# Final_Bread_Proofing_Box_2020_05_07_A.net
KiCad netlist of a schematic drawn in EAGLE
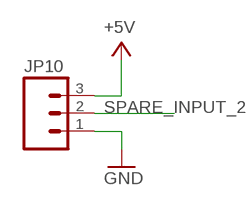
[diagram p0: schematic, sheet 1, part 1 of 2]
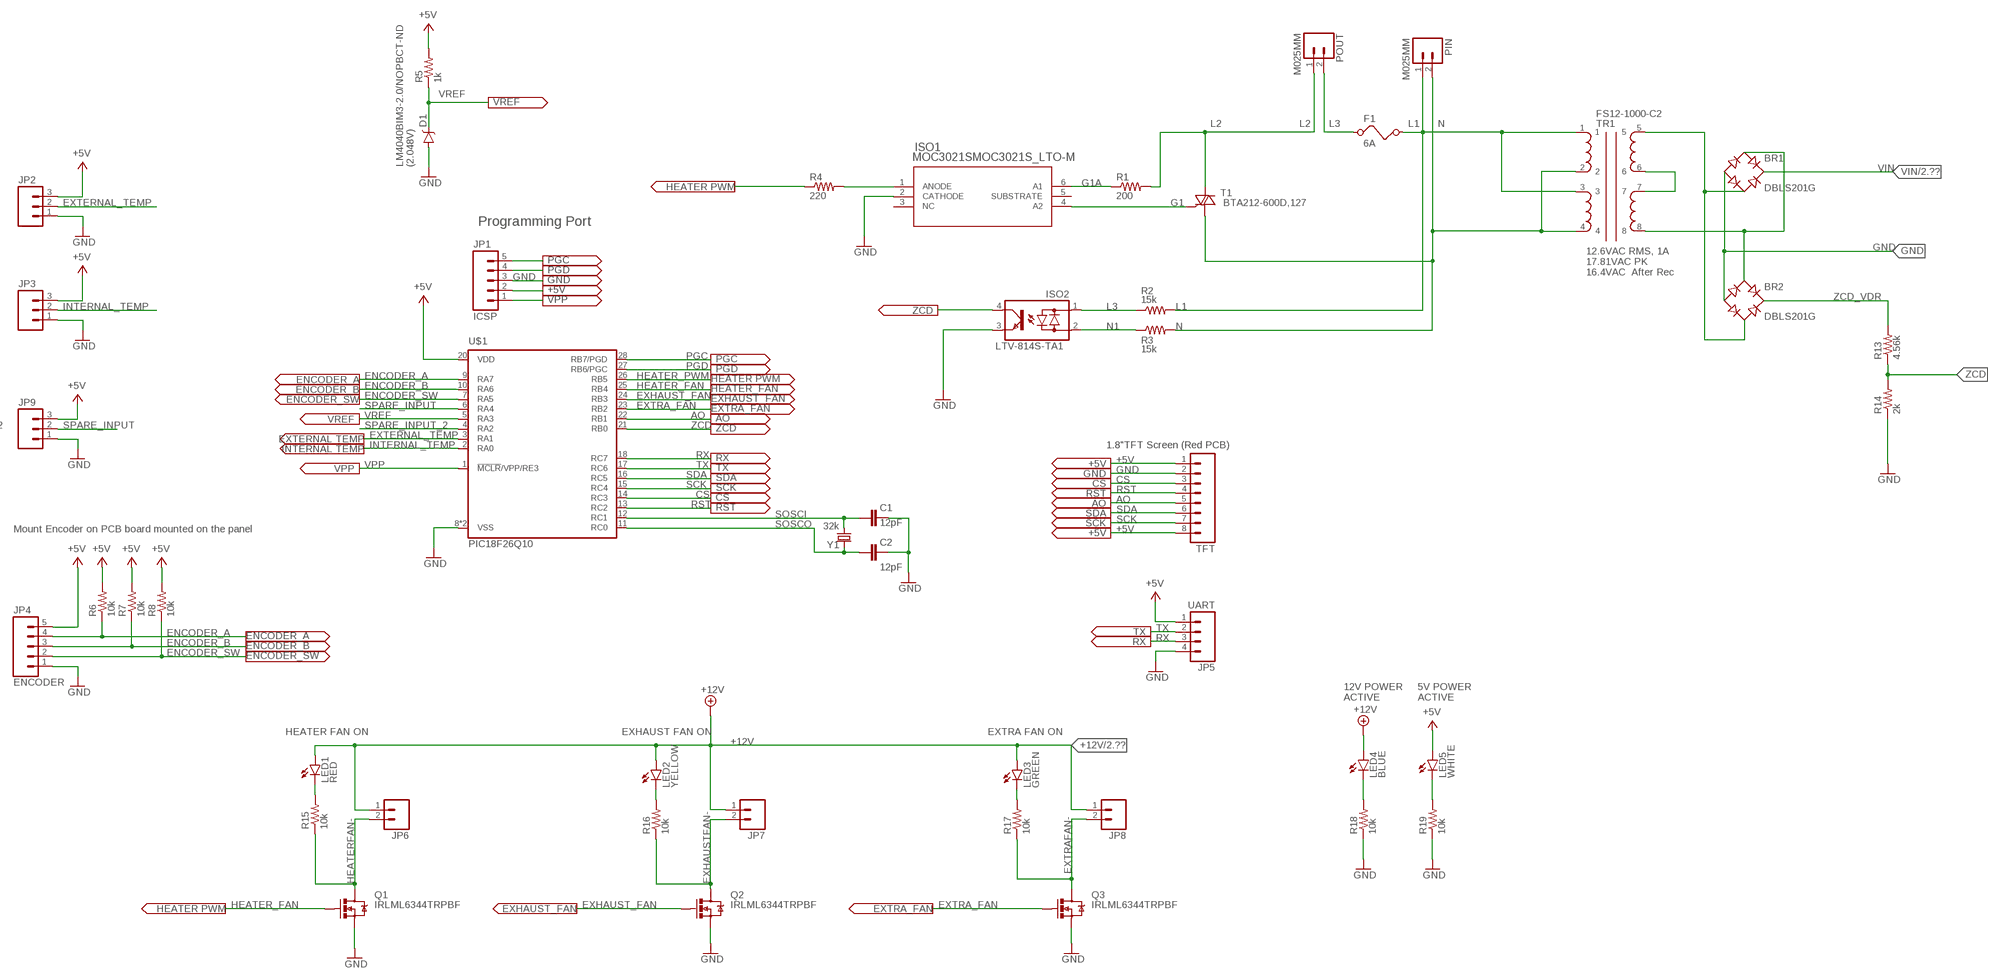
[diagram p1: schematic, sheet 1, part 2 of 2]
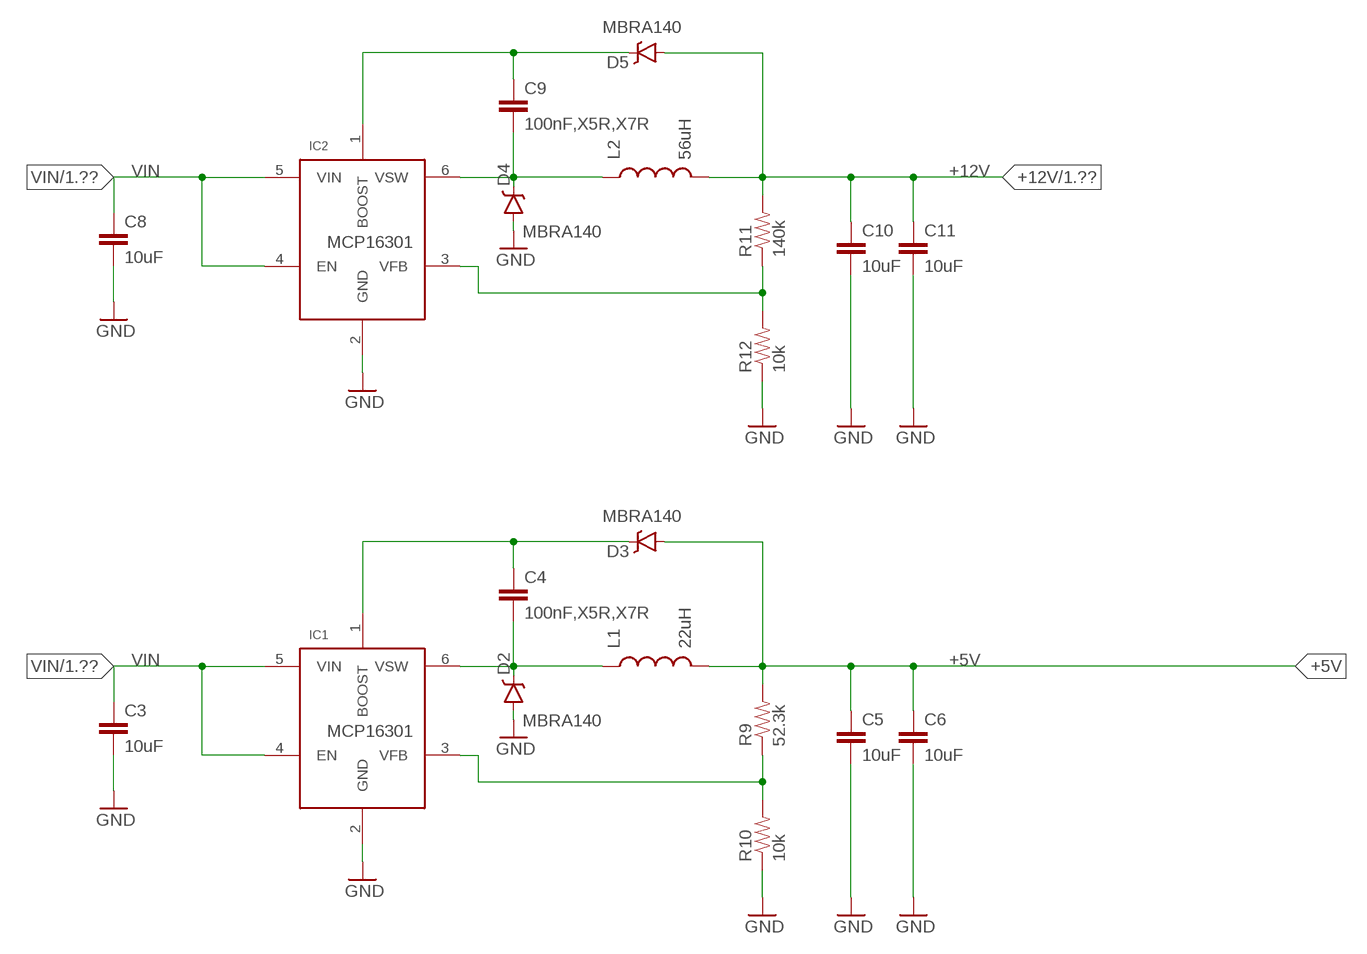
[diagram p2: schematic, sheet 2]

(export (version "E")
  (design (tool "Eeschema 10.0.6"))
  (components
    (comp (ref "BR1")
      (value "DBLS201G")
      (footprint "eagle-import:DBS")
      (libsource (lib "eagle-import") (part "DB?GLS201"))
    )
    (comp (ref "BR2")
      (value "DBLS201G")
      (footprint "eagle-import:DBS")
      (libsource (lib "eagle-import") (part "DB?GLS201"))
    )
    (comp (ref "C1")
      (value "12pF")
      (footprint "eagle-import:0805")
      (libsource (lib "eagle-import") (part "CAP0805"))
    )
    (comp (ref "C2")
      (value "12pF")
      (footprint "eagle-import:0805")
      (libsource (lib "eagle-import") (part "CAP0805"))
    )
    (comp (ref "D1")
      (value "V-REFERENCESMD")
      (footprint "eagle-import:SOT23-3")
      (libsource (lib "eagle-import") (part "V-REFERENCESMD"))
    )
    (comp (ref "F1")
      (value "6A")
      (footprint "eagle-import:FUSE")
      (libsource (lib "eagle-import") (part "FUSE"))
    )
    (comp (ref "ISO1")
      (value "MOC3021SMOC3021S_LTO-M")
      (footprint "eagle-import:MOC3021S_LTO-M")
      (fields
        (field (name "MANUFACTURER_PART_NUMBER") "MOC3021S")
        (field (name "COPYRIGHT") "Copyright (C) 2018 Accelerated Designs. All rights reserved")
      )
      (libsource (lib "eagle-import") (part "MOC3021SMOC3021S_LTO-M"))
    )
    (comp (ref "ISO2")
      (value "LTV-814S-TA1")
      (footprint "eagle-import:DIL4-SMD")
      (fields (field (name "MF") "VISHAY/TELEFUNKEN") (field (name "MPN") "SFH6206-3"))
      (libsource (lib "eagle-import") (part "SFH6206"))
    )
    (comp (ref "JP1")
      (value "ICSP")
      (footprint "eagle-import:1X05")
      (libsource (lib "eagle-import") (part "M05PTH"))
    )
    (comp (ref "JP2")
      (value "M03POLAR")
      (footprint "eagle-import:MOLEX-1X3")
      (libsource (lib "eagle-import") (part "M03POLAR"))
    )
    (comp (ref "JP3")
      (value "M03POLAR")
      (footprint "eagle-import:MOLEX-1X3")
      (libsource (lib "eagle-import") (part "M03POLAR"))
    )
    (comp (ref "JP4")
      (value "ENCODER")
      (footprint "eagle-import:1X05")
      (libsource (lib "eagle-import") (part "M05PTH"))
    )
    (comp (ref "JP5")
      (value "UART")
      (footprint "eagle-import:1X04_LOCK")
      (libsource (lib "eagle-import") (part "M04LOCK"))
    )
    (comp (ref "JP6")
      (value "M02POLAR_LOCK")
      (footprint "eagle-import:MOLEX-1X2_LOCK")
      (libsource (lib "eagle-import") (part "M02POLAR_LOCK"))
    )
    (comp (ref "JP7")
      (value "M02POLAR_LOCK")
      (footprint "eagle-import:MOLEX-1X2_LOCK")
      (libsource (lib "eagle-import") (part "M02POLAR_LOCK"))
    )
    (comp (ref "JP8")
      (value "M02POLAR_LOCK")
      (footprint "eagle-import:MOLEX-1X2_LOCK")
      (libsource (lib "eagle-import") (part "M02POLAR_LOCK"))
    )
    (comp (ref "JP9")
      (value "M03POLAR")
      (footprint "eagle-import:MOLEX-1X3")
      (libsource (lib "eagle-import") (part "M03POLAR"))
    )
    (comp (ref "JP10")
      (value "M03POLAR")
      (footprint "eagle-import:MOLEX-1X3")
      (libsource (lib "eagle-import") (part "M03POLAR"))
    )
    (comp (ref "LED1")
      (value "RED")
      (footprint "eagle-import:LED-1206")
      (libsource (lib "eagle-import") (part "LED1206"))
    )
    (comp (ref "LED2")
      (value "YELLOW")
      (footprint "eagle-import:LED-1206")
      (libsource (lib "eagle-import") (part "LED1206"))
    )
    (comp (ref "LED3")
      (value "GREEN")
      (footprint "eagle-import:LED-1206")
      (libsource (lib "eagle-import") (part "LED1206"))
    )
    (comp (ref "LED4")
      (value "BLUE")
      (footprint "eagle-import:LED-1206")
      (libsource (lib "eagle-import") (part "LED1206"))
    )
    (comp (ref "LED5")
      (value "WHITE")
      (footprint "eagle-import:LED-1206")
      (libsource (lib "eagle-import") (part "LED1206"))
    )
    (comp (ref "PIN")
      (value "M025MM")
      (footprint "eagle-import:SCREWTERMINAL-5MM-2")
      (libsource (lib "eagle-import") (part "M025MM"))
    )
    (comp (ref "POUT")
      (value "M025MM")
      (footprint "eagle-import:SCREWTERMINAL-5MM-2")
      (libsource (lib "eagle-import") (part "M025MM"))
    )
    (comp (ref "Q1")
      (value "IRLML6344TRPBF")
      (footprint "eagle-import:SOT323")
      (libsource (lib "eagle-import") (part "MOSFET-NCHANNEL2N7002PW"))
    )
    (comp (ref "Q2")
      (value "IRLML6344TRPBF")
      (footprint "eagle-import:SOT323")
      (libsource (lib "eagle-import") (part "MOSFET-NCHANNEL2N7002PW"))
    )
    (comp (ref "Q3")
      (value "IRLML6344TRPBF")
      (footprint "eagle-import:SOT323")
      (libsource (lib "eagle-import") (part "MOSFET-NCHANNEL2N7002PW"))
    )
    (comp (ref "R1")
      (value "200")
      (footprint "eagle-import:R2512")
      (libsource (lib "eagle-import") (part "R-US_R2512"))
    )
    (comp (ref "R2")
      (value "15k")
      (footprint "eagle-import:R2512")
      (libsource (lib "eagle-import") (part "R-US_R2512"))
    )
    (comp (ref "R3")
      (value "15k")
      (footprint "eagle-import:R2512")
      (libsource (lib "eagle-import") (part "R-US_R2512"))
    )
    (comp (ref "R4")
      (value "220")
      (footprint "eagle-import:1206")
      (libsource (lib "eagle-import") (part "RESISTOR1206"))
    )
    (comp (ref "R5")
      (value "1k")
      (footprint "eagle-import:1206")
      (libsource (lib "eagle-import") (part "RESISTOR1206"))
    )
    (comp (ref "R6")
      (value "10k")
      (footprint "eagle-import:1206")
      (libsource (lib "eagle-import") (part "RESISTOR1206"))
    )
    (comp (ref "R7")
      (value "10k")
      (footprint "eagle-import:1206")
      (libsource (lib "eagle-import") (part "RESISTOR1206"))
    )
    (comp (ref "R8")
      (value "10k")
      (footprint "eagle-import:1206")
      (libsource (lib "eagle-import") (part "RESISTOR1206"))
    )
    (comp (ref "R13")
      (value "4.56k")
      (footprint "eagle-import:1206")
      (libsource (lib "eagle-import") (part "RESISTOR1206"))
    )
    (comp (ref "R14")
      (value "2k")
      (footprint "eagle-import:1206")
      (libsource (lib "eagle-import") (part "RESISTOR1206"))
    )
    (comp (ref "R15")
      (value "10k")
      (footprint "eagle-import:1206")
      (libsource (lib "eagle-import") (part "RESISTOR1206"))
    )
    (comp (ref "R16")
      (value "10k")
      (footprint "eagle-import:1206")
      (libsource (lib "eagle-import") (part "RESISTOR1206"))
    )
    (comp (ref "R17")
      (value "10k")
      (footprint "eagle-import:1206")
      (libsource (lib "eagle-import") (part "RESISTOR1206"))
    )
    (comp (ref "R18")
      (value "10k")
      (footprint "eagle-import:1206")
      (libsource (lib "eagle-import") (part "RESISTOR1206"))
    )
    (comp (ref "R19")
      (value "10k")
      (footprint "eagle-import:1206")
      (libsource (lib "eagle-import") (part "RESISTOR1206"))
    )
    (comp (ref "T1")
      (value "BTA212-600D,127")
      (footprint "eagle-import:TO220BV")
      (libsource (lib "eagle-import") (part "BT138-V"))
    )
    (comp (ref "TFT")
      (value "M08LOCK")
      (footprint "eagle-import:1X08_LOCK")
      (libsource (lib "eagle-import") (part "M08LOCK"))
    )
    (comp (ref "TR1")
      (value "FS12-1000-C2")
      (footprint "eagle-import:FS12-1000-C2")
      (libsource (lib "eagle-import") (part "FS12-1000-C2"))
    )
    (comp (ref "U$1")
      (value "PIC18F26Q10")
      (footprint "eagle-import:SO28W")
      (libsource (lib "eagle-import") (part "PIC18F25K22SOIC"))
    )
    (comp (ref "Y1")
      (value "32k")
      (footprint "eagle-import:TC26V")
      (libsource (lib "eagle-import") (part "CRYSTALTC26V"))
    )
    (comp (ref "C3")
      (value "10uF")
      (footprint "eagle-import:1206")
      (libsource (lib "eagle-import") (part "CAP1206"))
    )
    (comp (ref "C4")
      (value "100nF,X5R,X7R")
      (footprint "eagle-import:1206")
      (libsource (lib "eagle-import") (part "CAP1206"))
    )
    (comp (ref "C5")
      (value "10uF")
      (footprint "eagle-import:1206")
      (libsource (lib "eagle-import") (part "CAP1206"))
    )
    (comp (ref "C6")
      (value "10uF")
      (footprint "eagle-import:1206")
      (libsource (lib "eagle-import") (part "CAP1206"))
    )
    (comp (ref "C8")
      (value "10uF")
      (footprint "eagle-import:1206")
      (libsource (lib "eagle-import") (part "CAP1206"))
    )
    (comp (ref "C9")
      (value "100nF,X5R,X7R")
      (footprint "eagle-import:1206")
      (libsource (lib "eagle-import") (part "CAP1206"))
    )
    (comp (ref "C10")
      (value "10uF")
      (footprint "eagle-import:1206")
      (libsource (lib "eagle-import") (part "CAP1206"))
    )
    (comp (ref "C11")
      (value "10uF")
      (footprint "eagle-import:1206")
      (libsource (lib "eagle-import") (part "CAP1206"))
    )
    (comp (ref "D2")
      (value "MBRA140")
      (footprint "eagle-import:SMA-DIODE")
      (libsource (lib "eagle-import") (part "DIODE-SCHOTTKY-MBRA140"))
    )
    (comp (ref "D3")
      (value "MBRA140")
      (footprint "eagle-import:SMA-DIODE")
      (libsource (lib "eagle-import") (part "DIODE-SCHOTTKY-MBRA140"))
    )
    (comp (ref "D4")
      (value "MBRA140")
      (footprint "eagle-import:SMA-DIODE")
      (libsource (lib "eagle-import") (part "DIODE-SCHOTTKY-MBRA140"))
    )
    (comp (ref "D5")
      (value "MBRA140")
      (footprint "eagle-import:SMA-DIODE")
      (libsource (lib "eagle-import") (part "DIODE-SCHOTTKY-MBRA140"))
    )
    (comp (ref "IC1")
      (value "MCP16301")
      (footprint "eagle-import:SOT23-6")
      (libsource (lib "eagle-import") (part "MCP16301"))
    )
    (comp (ref "IC2")
      (value "MCP16301")
      (footprint "eagle-import:SOT23-6")
      (libsource (lib "eagle-import") (part "MCP16301"))
    )
    (comp (ref "L1")
      (value "22uH")
      (footprint "eagle-import:1210")
      (libsource (lib "eagle-import") (part "INDUCTOR1210"))
    )
    (comp (ref "L2")
      (value "56uH")
      (footprint "eagle-import:1210")
      (libsource (lib "eagle-import") (part "INDUCTOR1210"))
    )
    (comp (ref "R9")
      (value "52.3k")
      (footprint "eagle-import:1206")
      (libsource (lib "eagle-import") (part "RESISTOR1206"))
    )
    (comp (ref "R10")
      (value "10k")
      (footprint "eagle-import:1206")
      (libsource (lib "eagle-import") (part "RESISTOR1206"))
    )
    (comp (ref "R11")
      (value "140k")
      (footprint "eagle-import:1206")
      (libsource (lib "eagle-import") (part "RESISTOR1206"))
    )
    (comp (ref "R12")
      (value "10k")
      (footprint "eagle-import:1206")
      (libsource (lib "eagle-import") (part "RESISTOR1206"))
    )
  )
  (nets
    (net (code "1") (name "+5V") (class "Default")
      (node (ref "C5") (pin "1") (pinfunction "1_1") (pintype "passive"))
      (node (ref "C6") (pin "1") (pinfunction "1_1") (pintype "passive"))
      (node (ref "D3") (pin "A") (pinfunction "A_A") (pintype "passive"))
      (node (ref "JP1") (pin "2") (pinfunction "2_2") (pintype "passive"))
      (node (ref "JP10") (pin "3") (pinfunction "3_3") (pintype "passive"))
      (node (ref "JP2") (pin "3") (pinfunction "3_3") (pintype "passive"))
      (node (ref "JP3") (pin "3") (pinfunction "3_3") (pintype "passive"))
      (node (ref "JP4") (pin "5") (pinfunction "5_5") (pintype "passive"))
      (node (ref "JP5") (pin "1") (pinfunction "1_1") (pintype "passive"))
      (node (ref "JP9") (pin "3") (pinfunction "3_3") (pintype "passive"))
      (node (ref "L1") (pin "2") (pinfunction "2_2") (pintype "passive"))
      (node (ref "LED5") (pin "A") (pinfunction "A_A") (pintype "passive"))
      (node (ref "R5") (pin "2") (pinfunction "2_2") (pintype "passive"))
      (node (ref "R6") (pin "2") (pinfunction "2_2") (pintype "passive"))
      (node (ref "R7") (pin "2") (pinfunction "2_2") (pintype "passive"))
      (node (ref "R8") (pin "2") (pinfunction "2_2") (pintype "passive"))
      (node (ref "R9") (pin "2") (pinfunction "2_2") (pintype "passive"))
      (node (ref "TFT") (pin "1") (pinfunction "1_1") (pintype "passive"))
      (node (ref "TFT") (pin "8") (pinfunction "8_8") (pintype "passive"))
      (node (ref "U$1") (pin "20") (pinfunction "VDD_20") (pintype "power_in"))
    )
    (net (code "2") (name "+12V") (class "Default")
      (node (ref "C10") (pin "1") (pinfunction "1_1") (pintype "passive"))
      (node (ref "C11") (pin "1") (pinfunction "1_1") (pintype "passive"))
      (node (ref "D5") (pin "A") (pinfunction "A_A") (pintype "passive"))
      (node (ref "JP6") (pin "1") (pinfunction "1_1") (pintype "passive"))
      (node (ref "JP7") (pin "1") (pinfunction "1_1") (pintype "passive"))
      (node (ref "JP8") (pin "1") (pinfunction "1_1") (pintype "passive"))
      (node (ref "L2") (pin "2") (pinfunction "2_2") (pintype "passive"))
      (node (ref "LED1") (pin "A") (pinfunction "A_A") (pintype "passive"))
      (node (ref "LED2") (pin "A") (pinfunction "A_A") (pintype "passive"))
      (node (ref "LED3") (pin "A") (pinfunction "A_A") (pintype "passive"))
      (node (ref "LED4") (pin "A") (pinfunction "A_A") (pintype "passive"))
      (node (ref "R11") (pin "2") (pinfunction "2_2") (pintype "passive"))
    )
    (net (code "3") (name "AO") (class "Default")
      (node (ref "TFT") (pin "5") (pinfunction "5_5") (pintype "passive"))
      (node (ref "U$1") (pin "22") (pinfunction "RB1_22") (pintype "bidirectional"))
    )
    (net (code "4") (name "CS") (class "Default")
      (node (ref "TFT") (pin "3") (pinfunction "3_3") (pintype "passive"))
      (node (ref "U$1") (pin "14") (pinfunction "RC3_14") (pintype "bidirectional"))
    )
    (net (code "5") (name "ENCODER_A") (class "Default")
      (node (ref "JP4") (pin "4") (pinfunction "4_4") (pintype "passive"))
      (node (ref "R6") (pin "1") (pinfunction "1_1") (pintype "passive"))
      (node (ref "U$1") (pin "9") (pinfunction "RA7_9") (pintype "bidirectional"))
    )
    (net (code "6") (name "ENCODER_B") (class "Default")
      (node (ref "JP4") (pin "3") (pinfunction "3_3") (pintype "passive"))
      (node (ref "R7") (pin "1") (pinfunction "1_1") (pintype "passive"))
      (node (ref "U$1") (pin "10") (pinfunction "RA6_10") (pintype "bidirectional"))
    )
    (net (code "7") (name "ENCODER_SW") (class "Default")
      (node (ref "JP4") (pin "2") (pinfunction "2_2") (pintype "passive"))
      (node (ref "R8") (pin "1") (pinfunction "1_1") (pintype "passive"))
      (node (ref "U$1") (pin "7") (pinfunction "RA5_7") (pintype "bidirectional"))
    )
    (net (code "8") (name "EXHAUSTFAN-") (class "Default")
      (node (ref "JP7") (pin "2") (pinfunction "2_2") (pintype "passive"))
      (node (ref "Q2") (pin "3") (pinfunction "D_3") (pintype "passive"))
      (node (ref "R16") (pin "1") (pinfunction "1_1") (pintype "passive"))
    )
    (net (code "9") (name "EXHAUST_FAN") (class "Default")
      (node (ref "Q2") (pin "1") (pinfunction "G_1") (pintype "passive"))
      (node (ref "U$1") (pin "24") (pinfunction "RB3_24") (pintype "bidirectional"))
    )
    (net (code "10") (name "EXTERNAL_TEMP") (class "Default")
      (node (ref "JP2") (pin "2") (pinfunction "2_2") (pintype "passive"))
      (node (ref "U$1") (pin "3") (pinfunction "RA1_3") (pintype "bidirectional"))
    )
    (net (code "11") (name "EXTRAFAN-") (class "Default")
      (node (ref "JP8") (pin "2") (pinfunction "2_2") (pintype "passive"))
      (node (ref "Q3") (pin "3") (pinfunction "D_3") (pintype "passive"))
      (node (ref "R17") (pin "1") (pinfunction "1_1") (pintype "passive"))
    )
    (net (code "12") (name "EXTRA_FAN") (class "Default")
      (node (ref "Q3") (pin "1") (pinfunction "G_1") (pintype "passive"))
      (node (ref "U$1") (pin "23") (pinfunction "RB2_23") (pintype "bidirectional"))
    )
    (net (code "13") (name "G1") (class "Default")
      (node (ref "ISO1") (pin "4") (pinfunction "A2_4") (pintype "passive"))
      (node (ref "T1") (pin "G") (pinfunction "G_G") (pintype "passive"))
    )
    (net (code "14") (name "G1A") (class "Default")
      (node (ref "ISO1") (pin "6") (pinfunction "A1_6") (pintype "passive"))
      (node (ref "R1") (pin "1") (pinfunction "1_1") (pintype "passive"))
    )
    (net (code "15") (name "GND") (class "Default")
      (node (ref "BR1") (pin "-") (pinfunction "-_-") (pintype "passive"))
      (node (ref "BR2") (pin "-") (pinfunction "-_-") (pintype "passive"))
      (node (ref "C1") (pin "2") (pinfunction "2_2") (pintype "passive"))
      (node (ref "C10") (pin "2") (pinfunction "2_2") (pintype "passive"))
      (node (ref "C11") (pin "2") (pinfunction "2_2") (pintype "passive"))
      (node (ref "C2") (pin "2") (pinfunction "2_2") (pintype "passive"))
      (node (ref "C3") (pin "2") (pinfunction "2_2") (pintype "passive"))
      (node (ref "C5") (pin "2") (pinfunction "2_2") (pintype "passive"))
      (node (ref "C6") (pin "2") (pinfunction "2_2") (pintype "passive"))
      (node (ref "C8") (pin "2") (pinfunction "2_2") (pintype "passive"))
      (node (ref "D1") (pin "2") (pinfunction "A_2") (pintype "passive"))
      (node (ref "D2") (pin "A") (pinfunction "A_A") (pintype "passive"))
      (node (ref "D4") (pin "A") (pinfunction "A_A") (pintype "passive"))
      (node (ref "IC1") (pin "2") (pinfunction "GND_2") (pintype "bidirectional"))
      (node (ref "IC2") (pin "2") (pinfunction "GND_2") (pintype "bidirectional"))
      (node (ref "ISO1") (pin "2") (pinfunction "CATHODE_2") (pintype "passive"))
      (node (ref "ISO2") (pin "3") (pinfunction "E_3") (pintype "passive"))
      (node (ref "JP1") (pin "3") (pinfunction "3_3") (pintype "passive"))
      (node (ref "JP10") (pin "1") (pinfunction "1_1") (pintype "passive"))
      (node (ref "JP2") (pin "1") (pinfunction "1_1") (pintype "passive"))
      (node (ref "JP3") (pin "1") (pinfunction "1_1") (pintype "passive"))
      (node (ref "JP4") (pin "1") (pinfunction "1_1") (pintype "passive"))
      (node (ref "JP5") (pin "4") (pinfunction "4_4") (pintype "passive"))
      (node (ref "JP9") (pin "1") (pinfunction "1_1") (pintype "passive"))
      (node (ref "Q1") (pin "2") (pinfunction "S_2") (pintype "passive"))
      (node (ref "Q2") (pin "2") (pinfunction "S_2") (pintype "passive"))
      (node (ref "Q3") (pin "2") (pinfunction "S_2") (pintype "passive"))
      (node (ref "R10") (pin "1") (pinfunction "1_1") (pintype "passive"))
      (node (ref "R12") (pin "1") (pinfunction "1_1") (pintype "passive"))
      (node (ref "R14") (pin "1") (pinfunction "1_1") (pintype "passive"))
      (node (ref "R18") (pin "1") (pinfunction "1_1") (pintype "passive"))
      (node (ref "R19") (pin "1") (pinfunction "1_1") (pintype "passive"))
      (node (ref "TFT") (pin "2") (pinfunction "2_2") (pintype "passive"))
      (node (ref "U$1") (pin "19") (pinfunction "VSS_19") (pintype "power_in"))
      (node (ref "U$1") (pin "8") (pinfunction "VSS_8") (pintype "power_in"))
    )
    (net (code "16") (name "HEATERFAN-") (class "Default")
      (node (ref "JP6") (pin "2") (pinfunction "2_2") (pintype "passive"))
      (node (ref "Q1") (pin "3") (pinfunction "D_3") (pintype "passive"))
      (node (ref "R15") (pin "1") (pinfunction "1_1") (pintype "passive"))
    )
    (net (code "17") (name "HEATER_FAN") (class "Default")
      (node (ref "Q1") (pin "1") (pinfunction "G_1") (pintype "passive"))
      (node (ref "U$1") (pin "25") (pinfunction "RB4_25") (pintype "bidirectional"))
    )
    (net (code "18") (name "HEATER_PWM") (class "Default")
      (node (ref "R4") (pin "1") (pinfunction "1_1") (pintype "passive"))
      (node (ref "U$1") (pin "26") (pinfunction "RB5_26") (pintype "bidirectional"))
    )
    (net (code "19") (name "INTERNAL_TEMP") (class "Default")
      (node (ref "JP3") (pin "2") (pinfunction "2_2") (pintype "passive"))
      (node (ref "U$1") (pin "2") (pinfunction "RA0_2") (pintype "bidirectional"))
    )
    (net (code "20") (name "L1") (class "Default")
      (node (ref "F1") (pin "2") (pinfunction "2_2") (pintype "passive"))
      (node (ref "PIN") (pin "1") (pinfunction "1_1") (pintype "passive"))
      (node (ref "R2") (pin "2") (pinfunction "2_2") (pintype "passive"))
      (node (ref "TR1") (pin "1") (pinfunction "1_1") (pintype "passive"))
      (node (ref "TR1") (pin "3") (pinfunction "3_3") (pintype "passive"))
    )
    (net (code "21") (name "L2") (class "Default")
      (node (ref "POUT") (pin "1") (pinfunction "1_1") (pintype "passive"))
      (node (ref "R1") (pin "2") (pinfunction "2_2") (pintype "passive"))
      (node (ref "T1") (pin "T2") (pinfunction "A2_T2") (pintype "passive"))
    )
    (net (code "22") (name "L3") (class "Default")
      (node (ref "F1") (pin "1") (pinfunction "1_1") (pintype "passive"))
      (node (ref "ISO2") (pin "1") (pinfunction "AC1_1") (pintype "passive"))
      (node (ref "POUT") (pin "2") (pinfunction "2_2") (pintype "passive"))
      (node (ref "R2") (pin "1") (pinfunction "1_1") (pintype "passive"))
    )
    (net (code "23") (name "N") (class "Default")
      (node (ref "PIN") (pin "2") (pinfunction "2_2") (pintype "passive"))
      (node (ref "R3") (pin "2") (pinfunction "2_2") (pintype "passive"))
      (node (ref "T1") (pin "T1") (pinfunction "A1_T1") (pintype "passive"))
      (node (ref "TR1") (pin "2") (pinfunction "2_2") (pintype "passive"))
      (node (ref "TR1") (pin "4") (pinfunction "4_4") (pintype "passive"))
    )
    (net (code "24") (name "N1") (class "Default")
      (node (ref "ISO2") (pin "2") (pinfunction "AC2_2") (pintype "passive"))
      (node (ref "R3") (pin "1") (pinfunction "1_1") (pintype "passive"))
    )
    (net (code "25") (name "Net-(BR1-PadAC1)") (class "Default")
      (node (ref "BR1") (pin "AC1") (pinfunction "AC1_AC1") (pintype "passive"))
      (node (ref "BR2") (pin "AC1") (pinfunction "AC1_AC1") (pintype "passive"))
      (node (ref "TR1") (pin "8") (pinfunction "8_8") (pintype "bidirectional"))
    )
    (net (code "26") (name "Net-(BR1-PadAC2)") (class "Default")
      (node (ref "BR1") (pin "AC2") (pinfunction "AC2_AC2") (pintype "passive"))
      (node (ref "BR2") (pin "AC2") (pinfunction "AC2_AC2") (pintype "passive"))
      (node (ref "TR1") (pin "5") (pinfunction "5_5") (pintype "bidirectional"))
    )
    (net (code "27") (name "Net-(IC1-BOOST)") (class "Default")
      (node (ref "C4") (pin "1") (pinfunction "1_1") (pintype "passive"))
      (node (ref "D3") (pin "C") (pinfunction "C_C") (pintype "passive"))
      (node (ref "IC1") (pin "1") (pinfunction "BOOST_1") (pintype "bidirectional"))
    )
    (net (code "28") (name "Net-(IC1-VFB)") (class "Default")
      (node (ref "IC1") (pin "3") (pinfunction "VFB_3") (pintype "bidirectional"))
      (node (ref "R10") (pin "2") (pinfunction "2_2") (pintype "passive"))
      (node (ref "R9") (pin "1") (pinfunction "1_1") (pintype "passive"))
    )
    (net (code "29") (name "Net-(IC1-VSW)") (class "Default")
      (node (ref "C4") (pin "2") (pinfunction "2_2") (pintype "passive"))
      (node (ref "D2") (pin "C") (pinfunction "C_C") (pintype "passive"))
      (node (ref "IC1") (pin "6") (pinfunction "VSW_6") (pintype "bidirectional"))
      (node (ref "L1") (pin "1") (pinfunction "1_1") (pintype "passive"))
    )
    (net (code "30") (name "Net-(IC2-BOOST)") (class "Default")
      (node (ref "C9") (pin "1") (pinfunction "1_1") (pintype "passive"))
      (node (ref "D5") (pin "C") (pinfunction "C_C") (pintype "passive"))
      (node (ref "IC2") (pin "1") (pinfunction "BOOST_1") (pintype "bidirectional"))
    )
    (net (code "31") (name "Net-(IC2-VFB)") (class "Default")
      (node (ref "IC2") (pin "3") (pinfunction "VFB_3") (pintype "bidirectional"))
      (node (ref "R11") (pin "1") (pinfunction "1_1") (pintype "passive"))
      (node (ref "R12") (pin "2") (pinfunction "2_2") (pintype "passive"))
    )
    (net (code "32") (name "Net-(IC2-VSW)") (class "Default")
      (node (ref "C9") (pin "2") (pinfunction "2_2") (pintype "passive"))
      (node (ref "D4") (pin "C") (pinfunction "C_C") (pintype "passive"))
      (node (ref "IC2") (pin "6") (pinfunction "VSW_6") (pintype "bidirectional"))
      (node (ref "L2") (pin "1") (pinfunction "1_1") (pintype "passive"))
    )
    (net (code "33") (name "Net-(ISO1-ANODE)") (class "Default")
      (node (ref "ISO1") (pin "1") (pinfunction "ANODE_1") (pintype "passive"))
      (node (ref "R4") (pin "2") (pinfunction "2_2") (pintype "passive"))
    )
    (net (code "34") (name "Net-(LED1-PadC)") (class "Default")
      (node (ref "LED1") (pin "C") (pinfunction "C_C") (pintype "passive"))
      (node (ref "R15") (pin "2") (pinfunction "2_2") (pintype "passive"))
    )
    (net (code "35") (name "Net-(LED2-PadC)") (class "Default")
      (node (ref "LED2") (pin "C") (pinfunction "C_C") (pintype "passive"))
      (node (ref "R16") (pin "2") (pinfunction "2_2") (pintype "passive"))
    )
    (net (code "36") (name "Net-(LED3-PadC)") (class "Default")
      (node (ref "LED3") (pin "C") (pinfunction "C_C") (pintype "passive"))
      (node (ref "R17") (pin "2") (pinfunction "2_2") (pintype "passive"))
    )
    (net (code "37") (name "Net-(LED4-PadC)") (class "Default")
      (node (ref "LED4") (pin "C") (pinfunction "C_C") (pintype "passive"))
      (node (ref "R18") (pin "2") (pinfunction "2_2") (pintype "passive"))
    )
    (net (code "38") (name "Net-(LED5-PadC)") (class "Default")
      (node (ref "LED5") (pin "C") (pinfunction "C_C") (pintype "passive"))
      (node (ref "R19") (pin "2") (pinfunction "2_2") (pintype "passive"))
    )
    (net (code "39") (name "Net-(TR1-Pad6)") (class "Default")
      (node (ref "TR1") (pin "6") (pinfunction "6_6") (pintype "bidirectional"))
      (node (ref "TR1") (pin "7") (pinfunction "7_7") (pintype "bidirectional"))
    )
    (net (code "40") (name "PGC") (class "Default")
      (node (ref "JP1") (pin "5") (pinfunction "5_5") (pintype "passive"))
      (node (ref "U$1") (pin "28") (pinfunction "RB7/PGD_28") (pintype "bidirectional"))
    )
    (net (code "41") (name "PGD") (class "Default")
      (node (ref "JP1") (pin "4") (pinfunction "4_4") (pintype "passive"))
      (node (ref "U$1") (pin "27") (pinfunction "RB6/PGC_27") (pintype "bidirectional"))
    )
    (net (code "42") (name "RST") (class "Default")
      (node (ref "TFT") (pin "4") (pinfunction "4_4") (pintype "passive"))
      (node (ref "U$1") (pin "13") (pinfunction "RC2_13") (pintype "bidirectional"))
    )
    (net (code "43") (name "RX") (class "Default")
      (node (ref "JP5") (pin "3") (pinfunction "3_3") (pintype "passive"))
      (node (ref "U$1") (pin "18") (pinfunction "RC7_18") (pintype "bidirectional"))
    )
    (net (code "44") (name "SCK") (class "Default")
      (node (ref "TFT") (pin "7") (pinfunction "7_7") (pintype "passive"))
      (node (ref "U$1") (pin "15") (pinfunction "RC4_15") (pintype "bidirectional"))
    )
    (net (code "45") (name "SDA") (class "Default")
      (node (ref "TFT") (pin "6") (pinfunction "6_6") (pintype "passive"))
      (node (ref "U$1") (pin "16") (pinfunction "RC5_16") (pintype "bidirectional"))
    )
    (net (code "46") (name "SOSCI") (class "Default")
      (node (ref "C1") (pin "1") (pinfunction "1_1") (pintype "passive"))
      (node (ref "U$1") (pin "12") (pinfunction "RC1_12") (pintype "bidirectional"))
      (node (ref "Y1") (pin "1") (pinfunction "1_1") (pintype "passive"))
    )
    (net (code "47") (name "SOSCO") (class "Default")
      (node (ref "C2") (pin "1") (pinfunction "1_1") (pintype "passive"))
      (node (ref "U$1") (pin "11") (pinfunction "RC0_11") (pintype "bidirectional"))
      (node (ref "Y1") (pin "2") (pinfunction "2_2") (pintype "passive"))
    )
    (net (code "48") (name "SPARE_INPUT") (class "Default")
      (node (ref "JP9") (pin "2") (pinfunction "2_2") (pintype "passive"))
      (node (ref "U$1") (pin "6") (pinfunction "RA4_6") (pintype "bidirectional"))
    )
    (net (code "49") (name "SPARE_INPUT_2") (class "Default")
      (node (ref "JP10") (pin "2") (pinfunction "2_2") (pintype "passive"))
      (node (ref "U$1") (pin "4") (pinfunction "RA2_4") (pintype "bidirectional"))
    )
    (net (code "50") (name "TX") (class "Default")
      (node (ref "JP5") (pin "2") (pinfunction "2_2") (pintype "passive"))
      (node (ref "U$1") (pin "17") (pinfunction "RC6_17") (pintype "bidirectional"))
    )
    (net (code "51") (name "VIN") (class "Default")
      (node (ref "BR1") (pin "+") (pinfunction "+_+") (pintype "passive"))
      (node (ref "C3") (pin "1") (pinfunction "1_1") (pintype "passive"))
      (node (ref "C8") (pin "1") (pinfunction "1_1") (pintype "passive"))
      (node (ref "IC1") (pin "4") (pinfunction "EN_4") (pintype "bidirectional"))
      (node (ref "IC1") (pin "5") (pinfunction "VIN_5") (pintype "bidirectional"))
      (node (ref "IC2") (pin "4") (pinfunction "EN_4") (pintype "bidirectional"))
      (node (ref "IC2") (pin "5") (pinfunction "VIN_5") (pintype "bidirectional"))
    )
    (net (code "52") (name "VPP") (class "Default")
      (node (ref "JP1") (pin "1") (pinfunction "1_1") (pintype "passive"))
      (node (ref "U$1") (pin "1") (pinfunction "~{MCLR}/VPP/RE3_1") (pintype "bidirectional"))
    )
    (net (code "53") (name "VREF") (class "Default")
      (node (ref "D1") (pin "1") (pinfunction "C_1") (pintype "passive"))
      (node (ref "R5") (pin "1") (pinfunction "1_1") (pintype "passive"))
      (node (ref "U$1") (pin "5") (pinfunction "RA3_5") (pintype "bidirectional"))
    )
    (net (code "54") (name "ZCD") (class "Default")
      (node (ref "ISO2") (pin "4") (pinfunction "C_4") (pintype "passive"))
      (node (ref "R13") (pin "1") (pinfunction "1_1") (pintype "passive"))
      (node (ref "R14") (pin "2") (pinfunction "2_2") (pintype "passive"))
      (node (ref "U$1") (pin "21") (pinfunction "RB0_21") (pintype "bidirectional"))
    )
    (net (code "55") (name "ZCD_VDR") (class "Default")
      (node (ref "BR2") (pin "+") (pinfunction "+_+") (pintype "passive"))
      (node (ref "R13") (pin "2") (pinfunction "2_2") (pintype "passive"))
    )
    (net (code "56") (name "unconnected-(ISO1-NC-Pad3)") (class "Default")
      (node (ref "ISO1") (pin "3") (pinfunction "NC_3") (pintype "passive"))
    )
    (net (code "57") (name "unconnected-(ISO1-SUBSTRATE-Pad5)") (class "Default")
      (node (ref "ISO1") (pin "5") (pinfunction "SUBSTRATE_5") (pintype "passive"))
    )
  )
)
